# bicyclelab-charger-4.net
KiCad netlist of a schematic drawn in EAGLE
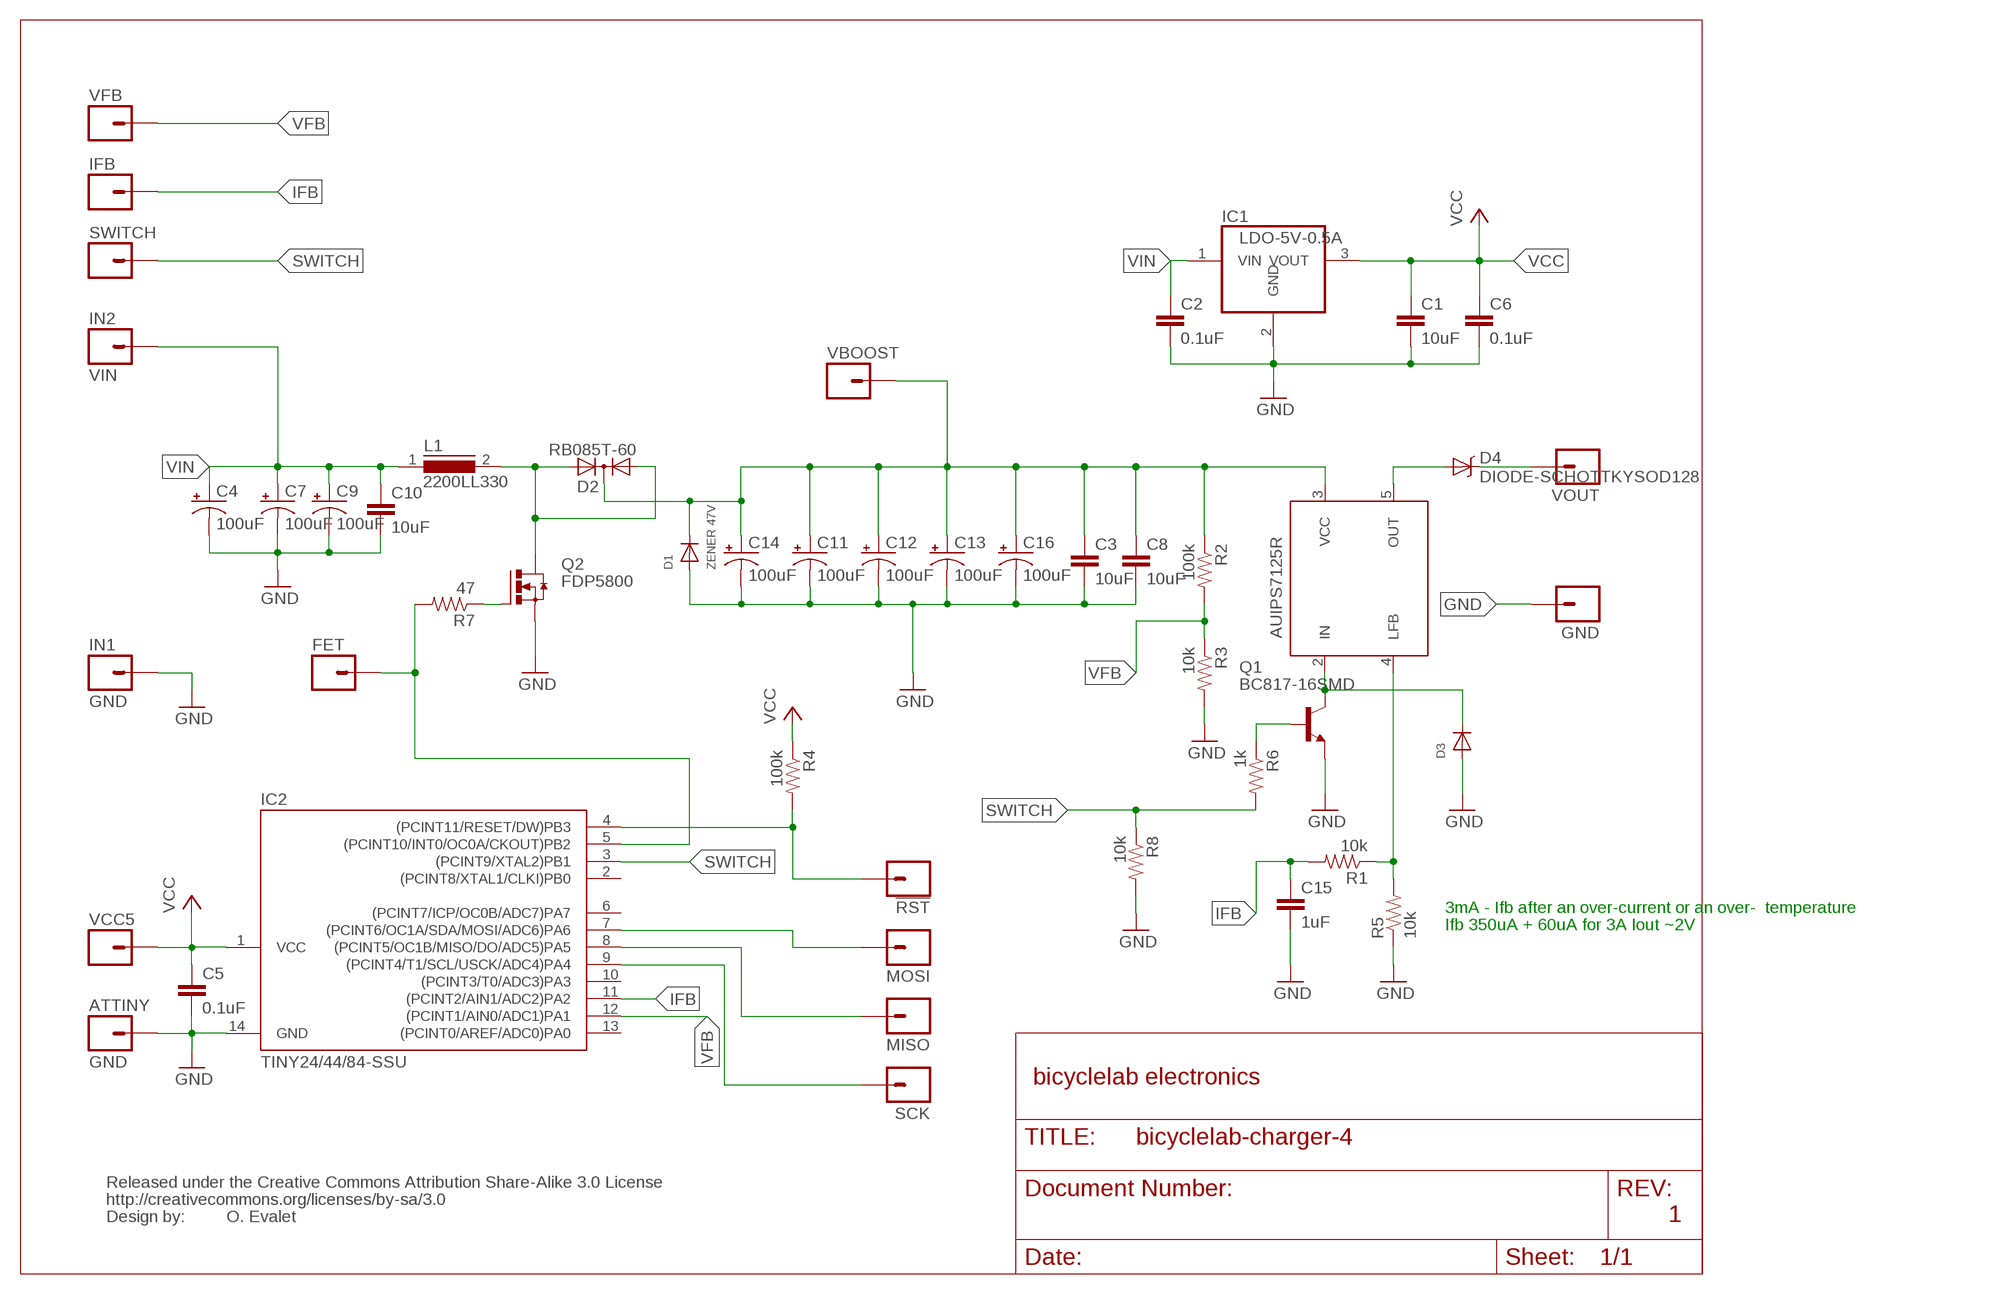
[diagram p0: schematic, sheet 1]

(export (version "E")
  (design (tool "Eeschema 10.0.6"))
  (components
    (comp (ref "!RST")
      (value "M01SMDNS")
      (footprint "eagle-import:1X01NS")
      (libsource (lib "eagle-import") (part "M01SMDNS"))
    )
    (comp (ref "ATTINY")
      (value "GND")
      (footprint "eagle-import:1X01NS")
      (libsource (lib "eagle-import") (part "M01SMDNS"))
    )
    (comp (ref "C1")
      (value "10uF")
      (footprint "eagle-import:0805")
      (libsource (lib "eagle-import") (part "bicyclelab_CAP0805"))
    )
    (comp (ref "C2")
      (value "0.1uF")
      (footprint "eagle-import:0805")
      (libsource (lib "eagle-import") (part "CAP0805"))
    )
    (comp (ref "C3")
      (value "10uF")
      (footprint "eagle-import:1210")
      (libsource (lib "eagle-import") (part "CAP1210"))
    )
    (comp (ref "C4")
      (value "100uF")
      (footprint "eagle-import:PANASONIC_D")
      (libsource (lib "eagle-import") (part "CPOL-USD"))
    )
    (comp (ref "C5")
      (value "0.1uF")
      (footprint "eagle-import:0805")
      (libsource (lib "eagle-import") (part "CAP0805"))
    )
    (comp (ref "C6")
      (value "0.1uF")
      (footprint "eagle-import:0805")
      (libsource (lib "eagle-import") (part "CAP0805"))
    )
    (comp (ref "C7")
      (value "100uF")
      (footprint "eagle-import:PANASONIC_D")
      (libsource (lib "eagle-import") (part "CPOL-USD"))
    )
    (comp (ref "C8")
      (value "10uF")
      (footprint "eagle-import:1210")
      (libsource (lib "eagle-import") (part "CAP1210"))
    )
    (comp (ref "C9")
      (value "100uF")
      (footprint "eagle-import:PANASONIC_D")
      (libsource (lib "eagle-import") (part "CPOL-USD"))
    )
    (comp (ref "C10")
      (value "10uF")
      (footprint "eagle-import:1210")
      (libsource (lib "eagle-import") (part "CAP1210"))
    )
    (comp (ref "C11")
      (value "100uF")
      (footprint "eagle-import:PANASONIC_D")
      (libsource (lib "eagle-import") (part "CPOL-USD"))
    )
    (comp (ref "C12")
      (value "100uF")
      (footprint "eagle-import:PANASONIC_D")
      (libsource (lib "eagle-import") (part "CPOL-USD"))
    )
    (comp (ref "C13")
      (value "100uF")
      (footprint "eagle-import:PANASONIC_D")
      (libsource (lib "eagle-import") (part "CPOL-USD"))
    )
    (comp (ref "C14")
      (value "100uF")
      (footprint "eagle-import:PANASONIC_D")
      (libsource (lib "eagle-import") (part "CPOL-USD"))
    )
    (comp (ref "C15")
      (value "1uF")
      (footprint "eagle-import:0805")
      (libsource (lib "eagle-import") (part "CAP0805"))
    )
    (comp (ref "C16")
      (value "100uF")
      (footprint "eagle-import:PANASONIC_D")
      (libsource (lib "eagle-import") (part "CPOL-USD"))
    )
    (comp (ref "D1")
      (value "ZENER 47V")
      (footprint "eagle-import:SOD-123")
      (libsource (lib "eagle-import") (part "DIODESOD-123"))
    )
    (comp (ref "D2")
      (value "RB085T-60")
      (footprint "eagle-import:TO220AB")
      (libsource (lib "eagle-import") (part "DIODE-2AC|CATO220H"))
    )
    (comp (ref "D3")
      (value "DIODESOD-123")
      (footprint "eagle-import:SOD-123")
      (libsource (lib "eagle-import") (part "DIODESOD-123"))
    )
    (comp (ref "D4")
      (value "DIODE-SCHOTTKYSOD128")
      (footprint "eagle-import:SOD-128")
      (libsource (lib "eagle-import") (part "DIODE-SCHOTTKYSOD128"))
    )
    (comp (ref "FET")
      (value "M01SMDNS")
      (footprint "eagle-import:1X01NS")
      (libsource (lib "eagle-import") (part "M01SMDNS"))
    )
    (comp (ref "GND")
      (value "M01SMDNS")
      (footprint "eagle-import:1X01NS")
      (libsource (lib "eagle-import") (part "M01SMDNS"))
    )
    (comp (ref "IC1")
      (value "LDO-5V-0.5A")
      (footprint "eagle-import:SOT223")
      (libsource (lib "eagle-import") (part "LDO-5V-0.5A"))
    )
    (comp (ref "IC2")
      (value "TINY24/44/84-SSU")
      (footprint "eagle-import:SOIC14")
      (libsource (lib "eagle-import") (part "TINY24/44/84-SSU"))
    )
    (comp (ref "IFB")
      (value "M01SMDNS")
      (footprint "eagle-import:1X01NS")
      (libsource (lib "eagle-import") (part "M01SMDNS"))
    )
    (comp (ref "IN1")
      (value "GND")
      (footprint "eagle-import:1X01NS")
      (libsource (lib "eagle-import") (part "M01SMDNS"))
    )
    (comp (ref "IN2")
      (value "VIN")
      (footprint "eagle-import:1X01")
      (libsource (lib "eagle-import") (part "M01PTH"))
    )
    (comp (ref "L1")
      (value "2200LL330")
      (footprint "eagle-import:DR175")
      (libsource (lib "eagle-import") (part "DR175"))
    )
    (comp (ref "MISO")
      (value "M01SMDNS")
      (footprint "eagle-import:1X01NS")
      (libsource (lib "eagle-import") (part "M01SMDNS"))
    )
    (comp (ref "MOSI")
      (value "M01SMDNS")
      (footprint "eagle-import:1X01NS")
      (libsource (lib "eagle-import") (part "M01SMDNS"))
    )
    (comp (ref "Q1")
      (value "BC817-16SMD")
      (footprint "eagle-import:SOT23-BEC")
      (libsource (lib "eagle-import") (part "BC817SMD-16"))
    )
    (comp (ref "Q2")
      (value "FDP5800")
      (footprint "eagle-import:TO220AH")
      (libsource (lib "eagle-import") (part "IRF3704"))
    )
    (comp (ref "R1")
      (value "10k")
      (footprint "eagle-import:0805")
      (libsource (lib "eagle-import") (part "RESISTOR"))
    )
    (comp (ref "R2")
      (value "100k")
      (footprint "eagle-import:0805")
      (libsource (lib "eagle-import") (part "RESISTOR"))
    )
    (comp (ref "R3")
      (value "10k")
      (footprint "eagle-import:0805")
      (libsource (lib "eagle-import") (part "RESISTOR"))
    )
    (comp (ref "R4")
      (value "100k")
      (footprint "eagle-import:0805")
      (libsource (lib "eagle-import") (part "RESISTOR"))
    )
    (comp (ref "R5")
      (value "10k")
      (footprint "eagle-import:0805")
      (libsource (lib "eagle-import") (part "RESISTOR"))
    )
    (comp (ref "R6")
      (value "1k")
      (footprint "eagle-import:0805")
      (libsource (lib "eagle-import") (part "RESISTOR"))
    )
    (comp (ref "R7")
      (value "47")
      (footprint "eagle-import:0805")
      (libsource (lib "eagle-import") (part "RESISTOR"))
    )
    (comp (ref "R8")
      (value "10k")
      (footprint "eagle-import:0805")
      (libsource (lib "eagle-import") (part "RESISTOR"))
    )
    (comp (ref "SCK")
      (value "M01SMDNS")
      (footprint "eagle-import:1X01NS")
      (libsource (lib "eagle-import") (part "M01SMDNS"))
    )
    (comp (ref "SWITCH")
      (value "M01SMDNS")
      (footprint "eagle-import:1X01NS")
      (libsource (lib "eagle-import") (part "M01SMDNS"))
    )
    (comp (ref "U$5")
      (value "CREATIVE_COMMONS")
      (footprint "eagle-import:CREATIVE_COMMONS")
      (libsource (lib "eagle-import") (part "CREATIVE_COMMONS"))
    )
    (comp (ref "U$8")
      (value "AUIPS7125R")
      (footprint "eagle-import:DPAK-5")
      (libsource (lib "eagle-import") (part "AUIPS7125R"))
    )
    (comp (ref "VBOOST")
      (value "M01SMDNS")
      (footprint "eagle-import:1X01NS")
      (libsource (lib "eagle-import") (part "M01SMDNS"))
    )
    (comp (ref "VCC5")
      (value "M01PTH")
      (footprint "eagle-import:1X01")
      (libsource (lib "eagle-import") (part "M01PTH"))
    )
    (comp (ref "VFB")
      (value "M01SMDNS")
      (footprint "eagle-import:1X01NS")
      (libsource (lib "eagle-import") (part "M01SMDNS"))
    )
    (comp (ref "VOUT")
      (value "M01PTH")
      (footprint "eagle-import:1X01")
      (libsource (lib "eagle-import") (part "M01PTH"))
    )
  )
  (nets
    (net (code "1") (name "GND") (class "Default")
      (node (ref "ATTINY") (pin "1") (pinfunction "1_1") (pintype "passive"))
      (node (ref "C1") (pin "2") (pinfunction "2_2") (pintype "passive"))
      (node (ref "C10") (pin "2") (pinfunction "2_2") (pintype "passive"))
      (node (ref "C11") (pin "-") (pinfunction "-_-") (pintype "passive"))
      (node (ref "C12") (pin "-") (pinfunction "-_-") (pintype "passive"))
      (node (ref "C13") (pin "-") (pinfunction "-_-") (pintype "passive"))
      (node (ref "C14") (pin "-") (pinfunction "-_-") (pintype "passive"))
      (node (ref "C15") (pin "2") (pinfunction "2_2") (pintype "passive"))
      (node (ref "C16") (pin "-") (pinfunction "-_-") (pintype "passive"))
      (node (ref "C2") (pin "2") (pinfunction "2_2") (pintype "passive"))
      (node (ref "C3") (pin "2") (pinfunction "2_2") (pintype "passive"))
      (node (ref "C4") (pin "-") (pinfunction "-_-") (pintype "passive"))
      (node (ref "C5") (pin "2") (pinfunction "2_2") (pintype "passive"))
      (node (ref "C6") (pin "2") (pinfunction "2_2") (pintype "passive"))
      (node (ref "C7") (pin "-") (pinfunction "-_-") (pintype "passive"))
      (node (ref "C8") (pin "2") (pinfunction "2_2") (pintype "passive"))
      (node (ref "C9") (pin "-") (pinfunction "-_-") (pintype "passive"))
      (node (ref "D1") (pin "A") (pinfunction "A_A") (pintype "passive"))
      (node (ref "D3") (pin "A") (pinfunction "A_A") (pintype "passive"))
      (node (ref "GND") (pin "1") (pinfunction "1_1") (pintype "passive"))
      (node (ref "IC1") (pin "2") (pinfunction "GND_2") (pintype "power_in"))
      (node (ref "IC2") (pin "14") (pinfunction "GND_14") (pintype "power_in"))
      (node (ref "IN1") (pin "1") (pinfunction "1_1") (pintype "passive"))
      (node (ref "Q1") (pin "E") (pinfunction "E_E") (pintype "passive"))
      (node (ref "Q2") (pin "E") (pinfunction "S_E") (pintype "passive"))
      (node (ref "R3") (pin "2") (pinfunction "2_2") (pintype "passive"))
      (node (ref "R5") (pin "1") (pinfunction "1_1") (pintype "passive"))
      (node (ref "R8") (pin "2") (pinfunction "2_2") (pintype "passive"))
    )
    (net (code "2") (name "IFB") (class "Default")
      (node (ref "C15") (pin "1") (pinfunction "1_1") (pintype "passive"))
      (node (ref "IC2") (pin "11") (pinfunction "(PCINT2/AIN1/ADC2)PA2_11") (pintype "bidirectional"))
      (node (ref "IFB") (pin "1") (pinfunction "1_1") (pintype "passive"))
      (node (ref "R1") (pin "2") (pinfunction "2_2") (pintype "passive"))
    )
    (net (code "3") (name "Net-(D4-A)") (class "Default")
      (node (ref "D4") (pin "2") (pinfunction "A_2") (pintype "passive"))
      (node (ref "U$8") (pin "5") (pinfunction "OUT_5") (pintype "output"))
    )
    (net (code "4") (name "Net-(D4-C)") (class "Default")
      (node (ref "D4") (pin "1") (pinfunction "C_1") (pintype "passive"))
      (node (ref "VOUT") (pin "1") (pinfunction "1_1") (pintype "passive"))
    )
    (net (code "5") (name "Net-(IC2-(PCINT4{slash}T1{slash}SCL{slash}USCK{slash}ADC4)PA4)") (class "Default")
      (node (ref "IC2") (pin "9") (pinfunction "(PCINT4/T1/SCL/USCK/ADC4)PA4_9") (pintype "bidirectional"))
      (node (ref "SCK") (pin "1") (pinfunction "1_1") (pintype "passive"))
    )
    (net (code "6") (name "Net-(IC2-(PCINT5{slash}OC1B{slash}MISO{slash}DO{slash}ADC5)PA5)") (class "Default")
      (node (ref "IC2") (pin "8") (pinfunction "(PCINT5/OC1B/MISO/DO/ADC5)PA5_8") (pintype "bidirectional"))
      (node (ref "MISO") (pin "1") (pinfunction "1_1") (pintype "passive"))
    )
    (net (code "7") (name "Net-(IC2-(PCINT6{slash}OC1A{slash}SDA{slash}MOSI{slash}ADC6)PA6)") (class "Default")
      (node (ref "IC2") (pin "7") (pinfunction "(PCINT6/OC1A/SDA/MOSI/ADC6)PA6_7") (pintype "bidirectional"))
      (node (ref "MOSI") (pin "1") (pinfunction "1_1") (pintype "passive"))
    )
    (net (code "8") (name "Net-(IC2-(PCINT10{slash}INT0{slash}OC0A{slash}CKOUT)PB2)") (class "Default")
      (node (ref "FET") (pin "1") (pinfunction "1_1") (pintype "passive"))
      (node (ref "IC2") (pin "5") (pinfunction "(PCINT10/INT0/OC0A/CKOUT)PB2_5") (pintype "bidirectional"))
      (node (ref "R7") (pin "2") (pinfunction "2_2") (pintype "passive"))
    )
    (net (code "9") (name "Net-(IC2-(PCINT11{slash}RESET{slash}DW)PB3)") (class "Default")
      (node (ref "!RST") (pin "1") (pinfunction "1_1") (pintype "passive"))
      (node (ref "IC2") (pin "4") (pinfunction "(PCINT11/RESET/DW)PB3_4") (pintype "bidirectional"))
      (node (ref "R4") (pin "2") (pinfunction "2_2") (pintype "passive"))
    )
    (net (code "10") (name "Net-(Q1-PadB)") (class "Default")
      (node (ref "Q1") (pin "B") (pinfunction "B_B") (pintype "passive"))
      (node (ref "R6") (pin "1") (pinfunction "1_1") (pintype "passive"))
    )
    (net (code "11") (name "Net-(Q2-D)") (class "Default")
      (node (ref "D2") (pin "A1") (pinfunction "A1_A1") (pintype "passive"))
      (node (ref "D2") (pin "A2") (pinfunction "A2_A2") (pintype "passive"))
      (node (ref "L1") (pin "2") (pinfunction "2_2") (pintype "passive"))
      (node (ref "Q2") (pin "C") (pinfunction "D_C") (pintype "passive"))
    )
    (net (code "12") (name "Net-(Q2-G)") (class "Default")
      (node (ref "Q2") (pin "B") (pinfunction "G_B") (pintype "passive"))
      (node (ref "R7") (pin "1") (pinfunction "1_1") (pintype "passive"))
    )
    (net (code "13") (name "Net-(U$8-IN)") (class "Default")
      (node (ref "D3") (pin "C") (pinfunction "C_C") (pintype "passive"))
      (node (ref "Q1") (pin "C") (pinfunction "C_C") (pintype "passive"))
      (node (ref "U$8") (pin "2") (pinfunction "IN_2") (pintype "input"))
    )
    (net (code "14") (name "Net-(U$8-LFB)") (class "Default")
      (node (ref "R1") (pin "1") (pinfunction "1_1") (pintype "passive"))
      (node (ref "R5") (pin "2") (pinfunction "2_2") (pintype "passive"))
      (node (ref "U$8") (pin "4") (pinfunction "LFB_4") (pintype "output"))
    )
    (net (code "15") (name "Net-(U$8-VCC)") (class "Default")
      (node (ref "C11") (pin "+") (pinfunction "+_+") (pintype "passive"))
      (node (ref "C12") (pin "+") (pinfunction "+_+") (pintype "passive"))
      (node (ref "C13") (pin "+") (pinfunction "+_+") (pintype "passive"))
      (node (ref "C14") (pin "+") (pinfunction "+_+") (pintype "passive"))
      (node (ref "C16") (pin "+") (pinfunction "+_+") (pintype "passive"))
      (node (ref "C3") (pin "1") (pinfunction "1_1") (pintype "passive"))
      (node (ref "C8") (pin "1") (pinfunction "1_1") (pintype "passive"))
      (node (ref "D1") (pin "C") (pinfunction "C_C") (pintype "passive"))
      (node (ref "D2") (pin "C") (pinfunction "C_C") (pintype "passive"))
      (node (ref "R2") (pin "1") (pinfunction "1_1") (pintype "passive"))
      (node (ref "U$8") (pin "3") (pinfunction "VCC_3") (pintype "input"))
      (node (ref "VBOOST") (pin "1") (pinfunction "1_1") (pintype "passive"))
    )
    (net (code "16") (name "SWITCH") (class "Default")
      (node (ref "IC2") (pin "3") (pinfunction "(PCINT9/XTAL2)PB1_3") (pintype "bidirectional"))
      (node (ref "R6") (pin "2") (pinfunction "2_2") (pintype "passive"))
      (node (ref "R8") (pin "1") (pinfunction "1_1") (pintype "passive"))
      (node (ref "SWITCH") (pin "1") (pinfunction "1_1") (pintype "passive"))
    )
    (net (code "17") (name "VCC") (class "Default")
      (node (ref "C1") (pin "1") (pinfunction "1_1") (pintype "passive"))
      (node (ref "C5") (pin "1") (pinfunction "1_1") (pintype "passive"))
      (node (ref "C6") (pin "1") (pinfunction "1_1") (pintype "passive"))
      (node (ref "IC1") (pin "3") (pinfunction "VOUT_3") (pintype "output"))
      (node (ref "IC2") (pin "1") (pinfunction "VCC_1") (pintype "power_in"))
      (node (ref "R4") (pin "1") (pinfunction "1_1") (pintype "passive"))
      (node (ref "VCC5") (pin "1") (pinfunction "1_1") (pintype "passive"))
    )
    (net (code "18") (name "VFB") (class "Default")
      (node (ref "IC2") (pin "12") (pinfunction "(PCINT1/AIN0/ADC1)PA1_12") (pintype "bidirectional"))
      (node (ref "R2") (pin "2") (pinfunction "2_2") (pintype "passive"))
      (node (ref "R3") (pin "1") (pinfunction "1_1") (pintype "passive"))
      (node (ref "VFB") (pin "1") (pinfunction "1_1") (pintype "passive"))
    )
    (net (code "19") (name "VIN") (class "Default")
      (node (ref "C10") (pin "1") (pinfunction "1_1") (pintype "passive"))
      (node (ref "C2") (pin "1") (pinfunction "1_1") (pintype "passive"))
      (node (ref "C4") (pin "+") (pinfunction "+_+") (pintype "passive"))
      (node (ref "C7") (pin "+") (pinfunction "+_+") (pintype "passive"))
      (node (ref "C9") (pin "+") (pinfunction "+_+") (pintype "passive"))
      (node (ref "IC1") (pin "1") (pinfunction "VIN_1") (pintype "input"))
      (node (ref "IN2") (pin "1") (pinfunction "1_1") (pintype "passive"))
      (node (ref "L1") (pin "1") (pinfunction "1_1") (pintype "passive"))
    )
    (net (code "20") (name "unconnected-(IC2-(PCINT0{slash}AREF{slash}ADC0)PA0-Pad13)") (class "Default")
      (node (ref "IC2") (pin "13") (pinfunction "(PCINT0/AREF/ADC0)PA0_13") (pintype "bidirectional"))
    )
    (net (code "21") (name "unconnected-(IC2-(PCINT3{slash}T0{slash}ADC3)PA3-Pad10)") (class "Default")
      (node (ref "IC2") (pin "10") (pinfunction "(PCINT3/T0/ADC3)PA3_10") (pintype "bidirectional"))
    )
    (net (code "22") (name "unconnected-(IC2-(PCINT7{slash}ICP{slash}OC0B{slash}ADC7)PA7-Pad6)") (class "Default")
      (node (ref "IC2") (pin "6") (pinfunction "(PCINT7/ICP/OC0B/ADC7)PA7_6") (pintype "bidirectional"))
    )
    (net (code "23") (name "unconnected-(IC2-(PCINT8{slash}XTAL1{slash}CLKI)PB0-Pad2)") (class "Default")
      (node (ref "IC2") (pin "2") (pinfunction "(PCINT8/XTAL1/CLKI)PB0_2") (pintype "bidirectional"))
    )
    (net (code "24") (name "unconnected-(U$8-NC-Pad1)") (class "Default")
      (node (ref "U$8") (pin "1") (pinfunction "NC_1") (pintype "no_connect"))
    )
  )
)
